# led1.net
KiCad netlist of a schematic drawn in Altium Designer
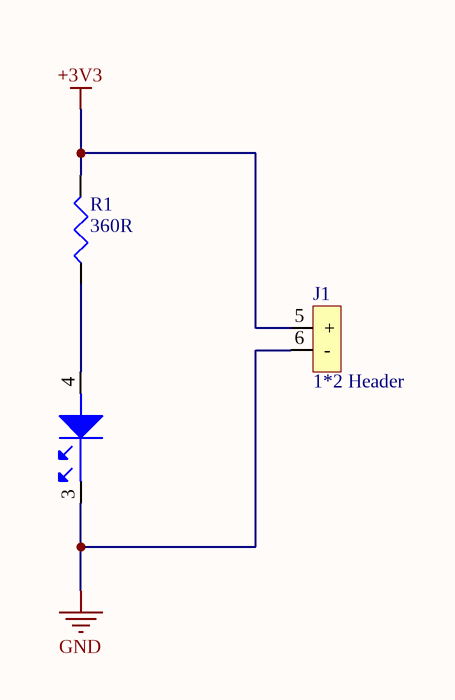
[diagram p0: led1.SchDoc]

(export (version "E")
  (design (tool "Eeschema 10.0.6"))
  (components
    (comp (ref "D1")
      (value "GREEN")
      (footprint "LED0603G")
      (description "LED GREEN ESS II SMD")
      (libsource (lib "led") (part "LNJ337W83RA"))
    )
    (comp (ref "J1")
      (value "1*2 Header")
      (footprint "HDR1X")
      (description "CONN HEADER VERT 2POS 2.54MM")
      (libsource (lib "led") (part "22-29-2021 (2)"))
    )
    (comp (ref "R1")
      (value "360R")
      (footprint "R0805")
      (description "Res Thick Film 0805 360 Ohm 1% 0.125W(1/8W) ±100ppm/C Molded SMD Automotive Paper T/R")
      (fields (field (name "TOLERANCE") "1%"))
      (libsource (lib "led") (part "CRCW0805360RFKEA"))
    )
  )
  (nets
    (net (code "1") (name "+3V3") (class "Default")
      (node (ref "J1") (pin "5") (pinfunction "+_5") (pintype "passive"))
      (node (ref "R1") (pin "R7") (pinfunction "360R_R7") (pintype "passive"))
    )
    (net (code "2") (name "GND") (class "Default")
      (node (ref "D1") (pin "3") (pinfunction "3_3") (pintype "passive"))
      (node (ref "J1") (pin "6") (pinfunction "-_6") (pintype "passive"))
    )
    (net (code "3") (name "Net-(D1-Pad4)") (class "Default")
      (node (ref "D1") (pin "4") (pinfunction "4_4") (pintype "passive"))
      (node (ref "R1") (pin "1") (pinfunction "1_1") (pintype "passive"))
    )
  )
)
